# MLX90393_Magnetometer_Breakout.net
KiCad netlist of a schematic drawn in EAGLE
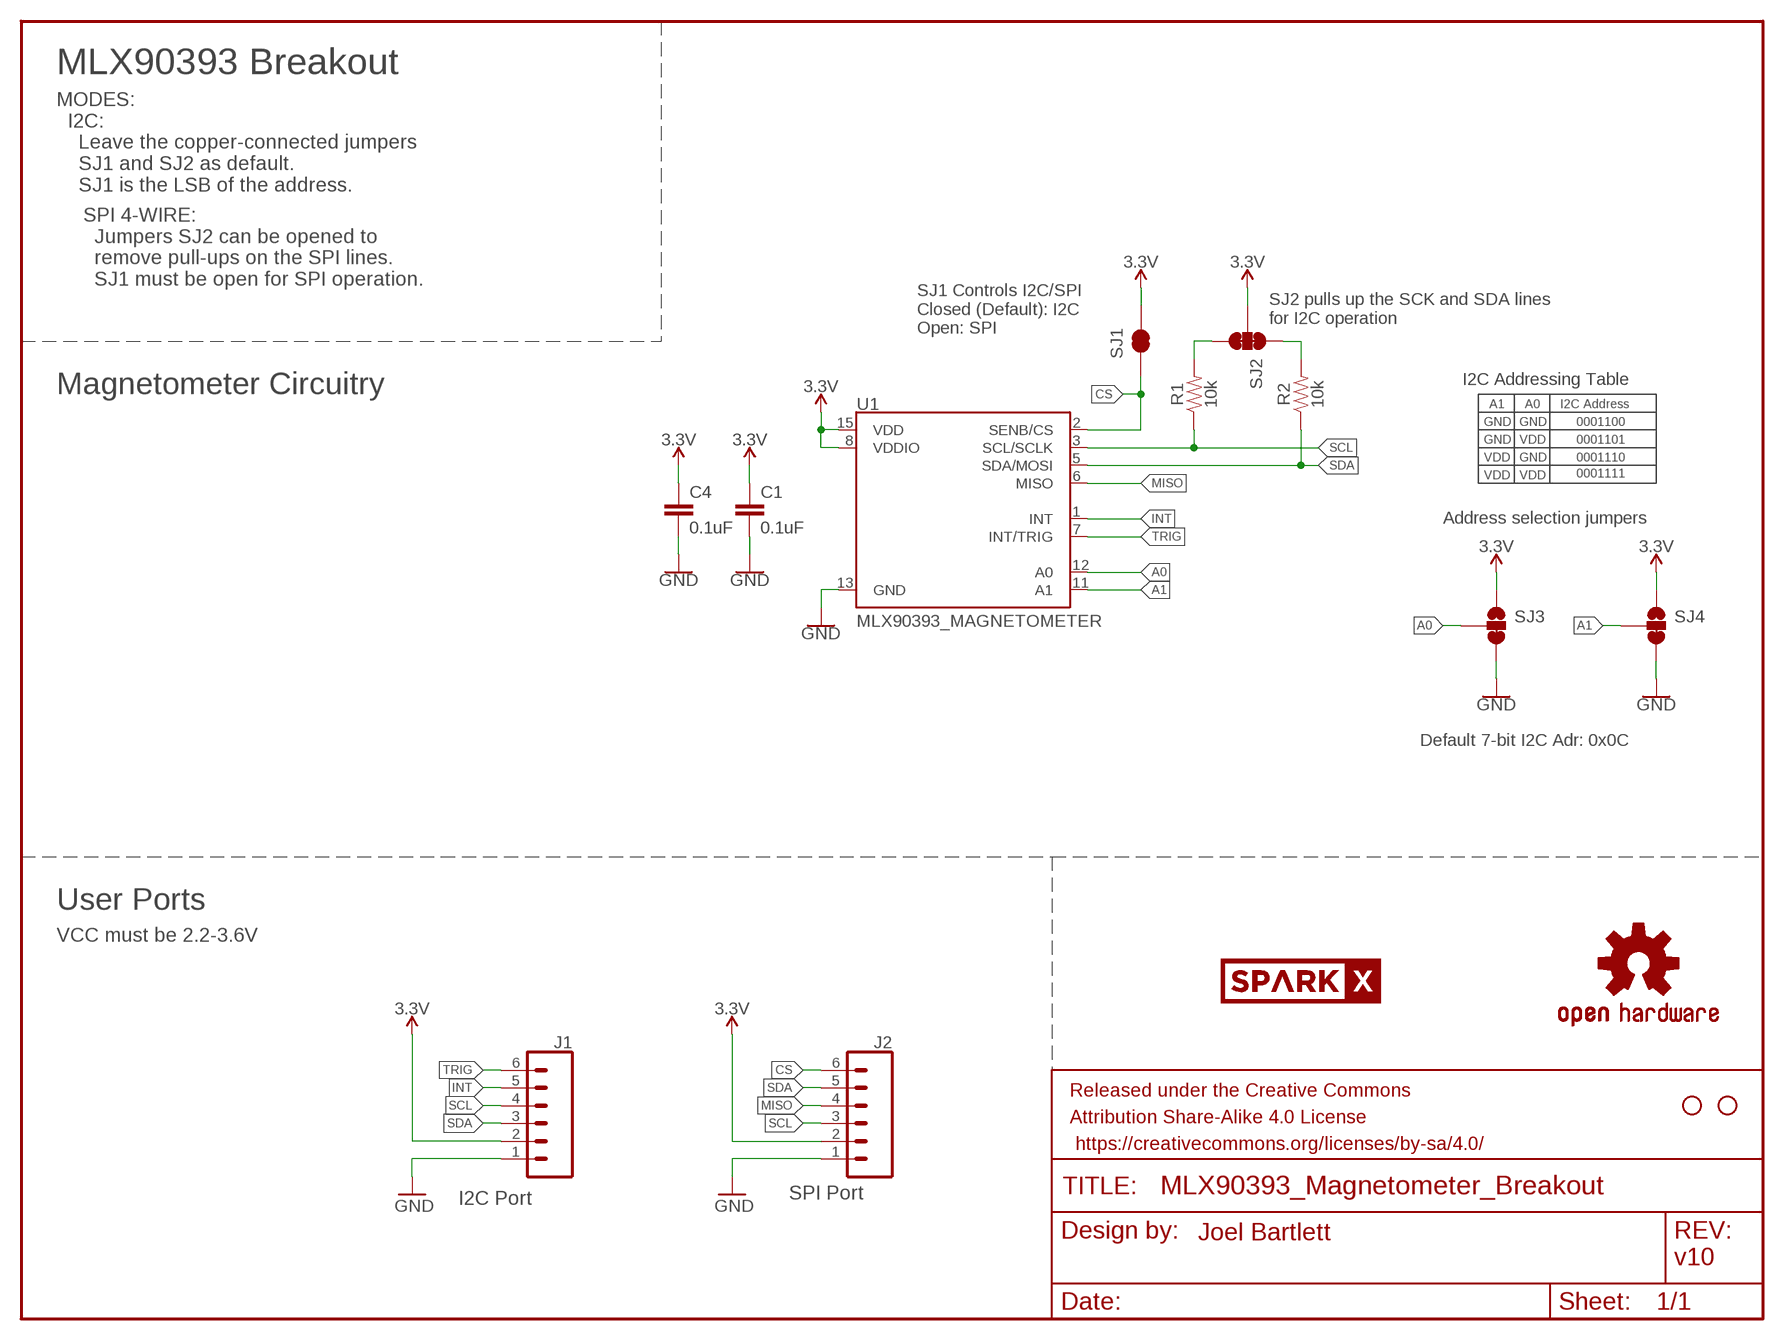
[diagram p0: schematic, sheet 1]

(export (version "E")
  (design (tool "Eeschema 10.0.6"))
  (components
    (comp (ref "C1")
      (value "0.1uF")
      (footprint "eagle-import:0603")
      (libsource (lib "eagle-import") (part "0.1UF-0603-25V-(+80/-20%)"))
    )
    (comp (ref "C4")
      (value "0.1uF")
      (footprint "eagle-import:0603")
      (libsource (lib "eagle-import") (part "0.1UF-0603-25V-(+80/-20%)"))
    )
    (comp (ref "FRAME2")
      (value "FRAME-LETTER")
      (footprint "eagle-import:CREATIVE_COMMONS")
      (libsource (lib "eagle-import") (part "FRAME-LETTER"))
    )
    (comp (ref "J1")
      (value "CONN_06NO_SILK_FEMALE_PTH")
      (footprint "eagle-import:1X06_NO_SILK")
      (libsource (lib "eagle-import") (part "CONN_06NO_SILK_FEMALE_PTH"))
    )
    (comp (ref "J2")
      (value "CONN_06NO_SILK_FEMALE_PTH")
      (footprint "eagle-import:1X06_NO_SILK")
      (libsource (lib "eagle-import") (part "CONN_06NO_SILK_FEMALE_PTH"))
    )
    (comp (ref "JP3")
      (value "STAND-OFF")
      (footprint "eagle-import:STAND-OFF")
      (libsource (lib "eagle-import") (part "STAND-OFF"))
    )
    (comp (ref "JP4")
      (value "STAND-OFF")
      (footprint "eagle-import:STAND-OFF")
      (libsource (lib "eagle-import") (part "STAND-OFF"))
    )
    (comp (ref "R1")
      (value "10k")
      (footprint "eagle-import:0603")
      (libsource (lib "eagle-import") (part "10KOHM-0603-1/10W-1%"))
    )
    (comp (ref "R2")
      (value "10k")
      (footprint "eagle-import:0603")
      (libsource (lib "eagle-import") (part "10KOHM-0603-1/10W-1%"))
    )
    (comp (ref "SJ1")
      (value "JUMPER-SMT_2_NC_TRACE_SILK")
      (footprint "eagle-import:SMT-JUMPER_2_NC_TRACE_SILK")
      (libsource (lib "eagle-import") (part "JUMPER-SMT_2_NC_TRACE_SILK"))
    )
    (comp (ref "SJ2")
      (value "JUMPER-PAD-3-NC_BY_TRACE")
      (footprint "eagle-import:PAD-JUMPER-3-3OF3_NC_BY_TRACE_YES_SILK_FULL_BOX")
      (libsource (lib "eagle-import") (part "JUMPER-PAD-3-NC_BY_TRACE"))
    )
    (comp (ref "SJ3")
      (value "JUMPER-SMT_3_1-NC_TRACE_SILK")
      (footprint "eagle-import:SMT-JUMPER_3_1-NC_TRACE_SILK")
      (libsource (lib "eagle-import") (part "JUMPER-SMT_3_1-NC_TRACE_SILK"))
    )
    (comp (ref "SJ4")
      (value "JUMPER-SMT_3_1-NC_TRACE_SILK")
      (footprint "eagle-import:SMT-JUMPER_3_1-NC_TRACE_SILK")
      (libsource (lib "eagle-import") (part "JUMPER-SMT_3_1-NC_TRACE_SILK"))
    )
    (comp (ref "U$1")
      (value "OSHW-LOGOS")
      (footprint "eagle-import:OSHW-LOGO-S")
      (libsource (lib "eagle-import") (part "OSHW-LOGOS"))
    )
    (comp (ref "U$2")
      (value "SPARKX-LOGO2")
      (footprint "eagle-import:SPARKX-TINY")
      (libsource (lib "eagle-import") (part "SPARKX-LOGO2"))
    )
    (comp (ref "U1")
      (value "MLX90393_MAGNETOMETER")
      (footprint "eagle-import:QFN-16")
      (libsource (lib "eagle-import") (part "MLX90393_MAGNETOMETER"))
    )
  )
  (nets
    (net (code "1") (name "3.3V") (class "Default")
      (node (ref "C1") (pin "1") (pinfunction "1_1") (pintype "passive"))
      (node (ref "C4") (pin "1") (pinfunction "1_1") (pintype "passive"))
      (node (ref "J1") (pin "2") (pinfunction "2_2") (pintype "passive"))
      (node (ref "J2") (pin "2") (pinfunction "2_2") (pintype "passive"))
      (node (ref "SJ1") (pin "2") (pinfunction "2_2") (pintype "passive"))
      (node (ref "SJ2") (pin "2") (pinfunction "2_2") (pintype "passive"))
      (node (ref "SJ3") (pin "1") (pinfunction "1_1") (pintype "passive"))
      (node (ref "SJ4") (pin "1") (pinfunction "1_1") (pintype "passive"))
      (node (ref "U1") (pin "15") (pinfunction "VDD_15") (pintype "bidirectional"))
      (node (ref "U1") (pin "8") (pinfunction "VDDIO_8") (pintype "bidirectional"))
    )
    (net (code "2") (name "A0") (class "Default")
      (node (ref "SJ3") (pin "2") (pinfunction "2_2") (pintype "passive"))
      (node (ref "U1") (pin "12") (pinfunction "A0_12") (pintype "bidirectional"))
    )
    (net (code "3") (name "A1") (class "Default")
      (node (ref "SJ4") (pin "2") (pinfunction "2_2") (pintype "passive"))
      (node (ref "U1") (pin "11") (pinfunction "A1_11") (pintype "bidirectional"))
    )
    (net (code "4") (name "CS") (class "Default")
      (node (ref "J2") (pin "6") (pinfunction "6_6") (pintype "passive"))
      (node (ref "SJ1") (pin "1") (pinfunction "1_1") (pintype "passive"))
      (node (ref "U1") (pin "2") (pinfunction "SENB/CS_2") (pintype "bidirectional"))
    )
    (net (code "5") (name "GND") (class "Default")
      (node (ref "C1") (pin "2") (pinfunction "2_2") (pintype "passive"))
      (node (ref "C4") (pin "2") (pinfunction "2_2") (pintype "passive"))
      (node (ref "J1") (pin "1") (pinfunction "1_1") (pintype "passive"))
      (node (ref "J2") (pin "1") (pinfunction "1_1") (pintype "passive"))
      (node (ref "SJ3") (pin "3") (pinfunction "3_3") (pintype "passive"))
      (node (ref "SJ4") (pin "3") (pinfunction "3_3") (pintype "passive"))
      (node (ref "U1") (pin "13") (pinfunction "GND_13") (pintype "bidirectional"))
    )
    (net (code "6") (name "INT") (class "Default")
      (node (ref "J1") (pin "5") (pinfunction "5_5") (pintype "passive"))
      (node (ref "U1") (pin "1") (pinfunction "INT_1") (pintype "bidirectional"))
    )
    (net (code "7") (name "MISO") (class "Default")
      (node (ref "J2") (pin "4") (pinfunction "4_4") (pintype "passive"))
      (node (ref "U1") (pin "6") (pinfunction "MISO_6") (pintype "bidirectional"))
    )
    (net (code "8") (name "Net-(R1-Pad2)") (class "Default")
      (node (ref "R1") (pin "2") (pinfunction "2_2") (pintype "passive"))
      (node (ref "SJ2") (pin "3") (pinfunction "3_3") (pintype "passive"))
    )
    (net (code "9") (name "Net-(R2-Pad2)") (class "Default")
      (node (ref "R2") (pin "2") (pinfunction "2_2") (pintype "passive"))
      (node (ref "SJ2") (pin "1") (pinfunction "1_1") (pintype "passive"))
    )
    (net (code "10") (name "SCL") (class "Default")
      (node (ref "J1") (pin "4") (pinfunction "4_4") (pintype "passive"))
      (node (ref "J2") (pin "3") (pinfunction "3_3") (pintype "passive"))
      (node (ref "R1") (pin "1") (pinfunction "1_1") (pintype "passive"))
      (node (ref "U1") (pin "3") (pinfunction "SCL/SCLK_3") (pintype "bidirectional"))
    )
    (net (code "11") (name "SDA") (class "Default")
      (node (ref "J1") (pin "3") (pinfunction "3_3") (pintype "passive"))
      (node (ref "J2") (pin "5") (pinfunction "5_5") (pintype "passive"))
      (node (ref "R2") (pin "1") (pinfunction "1_1") (pintype "passive"))
      (node (ref "U1") (pin "5") (pinfunction "SDA/MOSI_5") (pintype "bidirectional"))
    )
    (net (code "12") (name "TRIG") (class "Default")
      (node (ref "J1") (pin "6") (pinfunction "6_6") (pintype "passive"))
      (node (ref "U1") (pin "7") (pinfunction "INT/TRIG_7") (pintype "bidirectional"))
    )
  )
)
